# Project_Node_Sensors.net
KiCad netlist of a schematic drawn in Altium Designer
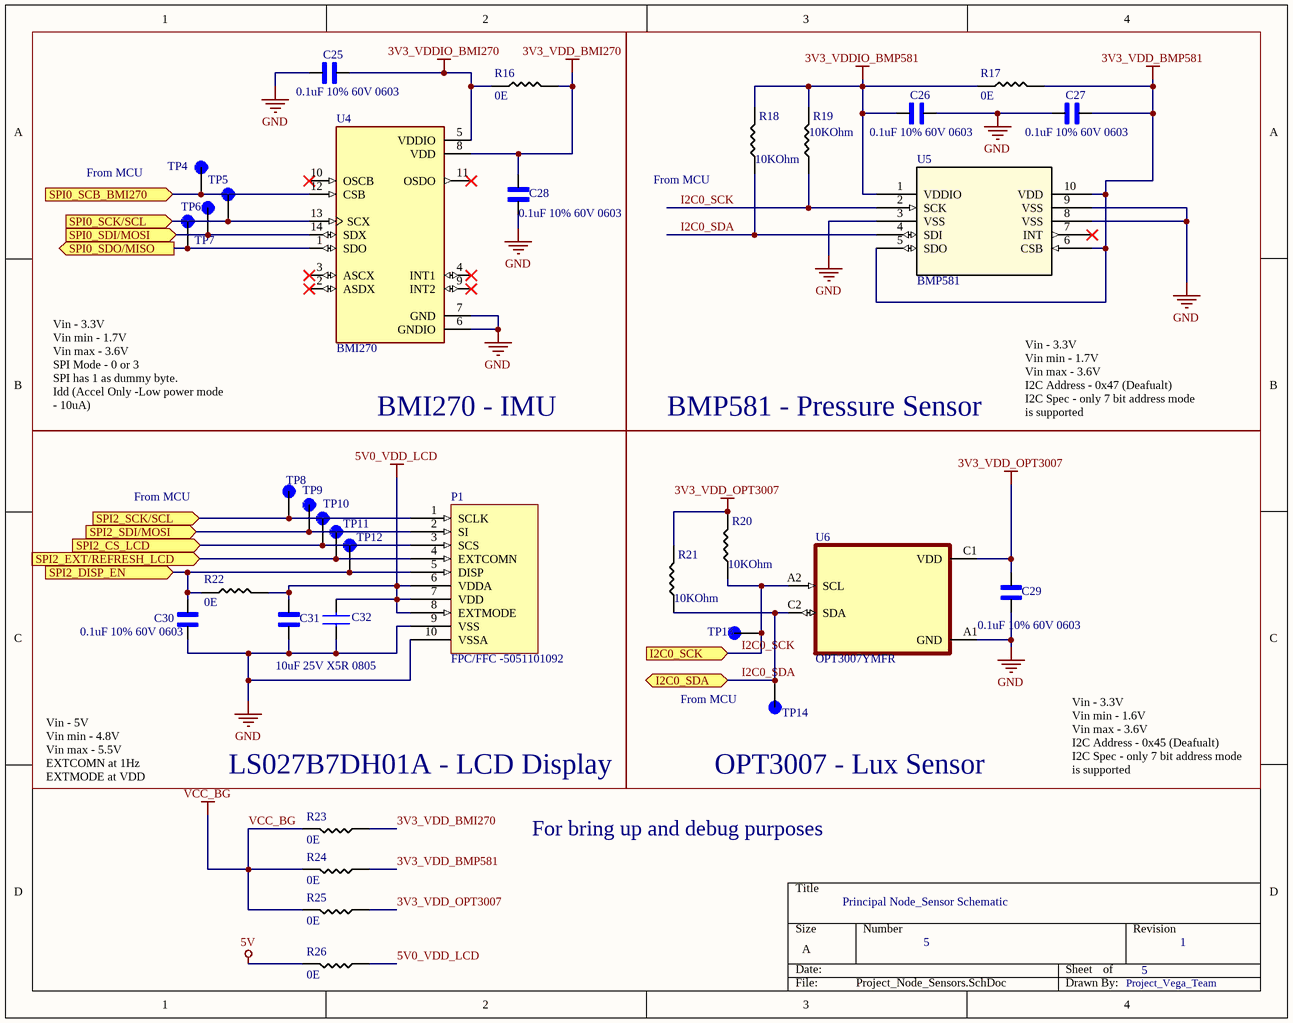
[diagram p0: Project_Node_Sensors.SchDoc]

(export (version "E")
  (design (tool "Eeschema 10.0.6"))
  (components
    (comp (ref "C25")
      (value "0.1uF 10% 60V 0603")
      (footprint "CAPC1608X90")
      (description "0.1 ÂµF Â±10% 50V Ceramic Capacitor X7R 0603 (1608 Metric)")
      (fields (field (name "MF") "Yageo") (field (name "MP") "CC0603KRX7R9BB104"))
      (libsource (lib "") (part "CC0603KRX7R9BB104_1"))
    )
    (comp (ref "C26")
      (value "0.1uF 10% 60V 0603")
      (footprint "CAPC1608X90")
      (description "0.1 ÂµF Â±10% 50V Ceramic Capacitor X7R 0603 (1608 Metric)")
      (fields (field (name "MF") "Yageo") (field (name "MP") "CC0603KRX7R9BB104"))
      (libsource (lib "") (part "CC0603KRX7R9BB104_1"))
    )
    (comp (ref "C27")
      (value "0.1uF 10% 60V 0603")
      (footprint "CAPC1608X90")
      (description "0.1 ÂµF Â±10% 50V Ceramic Capacitor X7R 0603 (1608 Metric)")
      (fields (field (name "MF") "Yageo") (field (name "MP") "CC0603KRX7R9BB104"))
      (libsource (lib "") (part "CC0603KRX7R9BB104_1"))
    )
    (comp (ref "C28")
      (value "0.1uF 10% 60V 0603")
      (footprint "CAPC1608X90")
      (description "0.1 ÂµF Â±10% 50V Ceramic Capacitor X7R 0603 (1608 Metric)")
      (fields (field (name "MF") "Yageo") (field (name "MP") "CC0603KRX7R9BB104"))
      (libsource (lib "") (part "CC0603KRX7R9BB104_2"))
    )
    (comp (ref "C29")
      (value "0.1uF 10% 60V 0603")
      (footprint "CAPC1608X90")
      (description "0.1 ÂµF Â±10% 50V Ceramic Capacitor X7R 0603 (1608 Metric)")
      (fields (field (name "MF") "Yageo") (field (name "MP") "CC0603KRX7R9BB104"))
      (libsource (lib "Project_Vega") (part "CC0603KRX7R9BB104"))
    )
    (comp (ref "C30")
      (value "0.1uF 10% 60V 0603")
      (footprint "CAPC1608X90")
      (description "0.1 ÂµF Â±10% 50V Ceramic Capacitor X7R 0603 (1608 Metric)")
      (fields (field (name "MF") "Yageo") (field (name "MP") "CC0603KRX7R9BB104"))
      (libsource (lib "Project_Vega") (part "CC0603KRX7R9BB104"))
    )
    (comp (ref "C31")
      (value "0.1uF 10% 60V 0603")
      (footprint "CAPC1608X90")
      (description "0.1 ÂµF Â±10% 50V Ceramic Capacitor X7R 0603 (1608 Metric)")
      (fields (field (name "MF") "Yageo") (field (name "MP") "CC0603KRX7R9BB104"))
      (libsource (lib "Project_Vega") (part "CC0603KRX7R9BB104"))
    )
    (comp (ref "C32")
      (value "10uF 25V X5R 0805")
      (footprint "CAP_0805_2mmX1.25mm")
      (description "Multilayer Ceramic Capacitor, 10 uF, 25 V, +/- 10%, X5R, 0805 [2012 Metric]")
      (fields
        (field (name "MANUFACTURER") "Murata")
        (field (name "MANUFACTURER PART NUMBER") "GRM21BR61E106KA73K")
      )
      (libsource (lib "Project_Vega") (part "GRM21BR61E106KA73K"))
    )
    (comp (ref "P1")
      (value "FPC/FFC -5051101092")
      (footprint "CON_5051101092_MOL")
      (description "10 Position FFC, FPC Connector Contacts, Bottom 0.020\" (0.50mm) Surface Mount, Right Angle")
      (libsource (lib "Project_Vega") (part "5051101092"))
    )
    (comp (ref "R16")
      (value "0E")
      (footprint "1206_Passive_Resitor")
      (description "10 kOhms ±5% 0.25W, 1/4W Chip Resistor 1206 (3216 Metric) Automotive AEC-Q200 Thick Film")
      (fields (field (name "MFR PART #") "RMCF1206FT10K0") (field (name "LCSC PART#") "C17902"))
      (libsource (lib "ECEN5730Lib_2023_05_DS") (part "R_10KOhm_1206"))
    )
    (comp (ref "R17")
      (value "0E")
      (footprint "1206_Passive_Resitor")
      (description "10 kOhms ±5% 0.25W, 1/4W Chip Resistor 1206 (3216 Metric) Automotive AEC-Q200 Thick Film")
      (fields (field (name "MFR PART #") "RMCF1206FT10K0") (field (name "LCSC PART#") "C17902"))
      (libsource (lib "ECEN5730Lib_2023_05_DS") (part "R_10KOhm_1206"))
    )
    (comp (ref "R18")
      (value "10KOhm")
      (footprint "1206_Passive_Resitor")
      (description "10 kOhms ±5% 0.25W, 1/4W Chip Resistor 1206 (3216 Metric) Automotive AEC-Q200 Thick Film")
      (fields (field (name "MFR PART #") "RMCF1206FT10K0") (field (name "LCSC PART#") "C17902"))
      (libsource (lib "ECEN5730Lib_2023_05_DS") (part "R_10KOhm_1206"))
    )
    (comp (ref "R19")
      (value "10KOhm")
      (footprint "1206_Passive_Resitor")
      (description "10 kOhms ±5% 0.25W, 1/4W Chip Resistor 1206 (3216 Metric) Automotive AEC-Q200 Thick Film")
      (fields (field (name "MFR PART #") "RMCF1206FT10K0") (field (name "LCSC PART#") "C17902"))
      (libsource (lib "ECEN5730Lib_2023_05_DS") (part "R_10KOhm_1206"))
    )
    (comp (ref "R20")
      (value "10KOhm")
      (footprint "1206_Passive_Resitor")
      (description "10 kOhms ±5% 0.25W, 1/4W Chip Resistor 1206 (3216 Metric) Automotive AEC-Q200 Thick Film")
      (fields (field (name "MFR PART #") "RMCF1206FT10K0") (field (name "LCSC PART#") "C17902"))
      (libsource (lib "ECEN5730Lib_2023_05_DS") (part "R_10KOhm_1206"))
    )
    (comp (ref "R21")
      (value "10KOhm")
      (footprint "1206_Passive_Resitor")
      (description "10 kOhms ±5% 0.25W, 1/4W Chip Resistor 1206 (3216 Metric) Automotive AEC-Q200 Thick Film")
      (fields (field (name "MFR PART #") "RMCF1206FT10K0") (field (name "LCSC PART#") "C17902"))
      (libsource (lib "ECEN5730Lib_2023_05_DS") (part "R_10KOhm_1206"))
    )
    (comp (ref "R22")
      (value "0E")
      (footprint "1206_Passive_Resitor")
      (description "10 kOhms ±5% 0.25W, 1/4W Chip Resistor 1206 (3216 Metric) Automotive AEC-Q200 Thick Film")
      (fields (field (name "MFR PART #") "RMCF1206FT10K0") (field (name "LCSC PART#") "C17902"))
      (libsource (lib "ECEN5730Lib_2023_05_DS") (part "R_10KOhm_1206"))
    )
    (comp (ref "R23")
      (value "0E")
      (footprint "1206_Passive_Resitor")
      (description "10 kOhms ±5% 0.25W, 1/4W Chip Resistor 1206 (3216 Metric) Automotive AEC-Q200 Thick Film")
      (fields (field (name "MFR PART #") "RMCF1206FT10K0") (field (name "LCSC PART#") "C17902"))
      (libsource (lib "ECEN5730Lib_2023_05_DS") (part "R_10KOhm_1206"))
    )
    (comp (ref "R24")
      (value "0E")
      (footprint "1206_Passive_Resitor")
      (description "10 kOhms ±5% 0.25W, 1/4W Chip Resistor 1206 (3216 Metric) Automotive AEC-Q200 Thick Film")
      (fields (field (name "MFR PART #") "RMCF1206FT10K0") (field (name "LCSC PART#") "C17902"))
      (libsource (lib "ECEN5730Lib_2023_05_DS") (part "R_10KOhm_1206"))
    )
    (comp (ref "R25")
      (value "0E")
      (footprint "1206_Passive_Resitor")
      (description "10 kOhms ±5% 0.25W, 1/4W Chip Resistor 1206 (3216 Metric) Automotive AEC-Q200 Thick Film")
      (fields (field (name "MFR PART #") "RMCF1206FT10K0") (field (name "LCSC PART#") "C17902"))
      (libsource (lib "ECEN5730Lib_2023_05_DS") (part "R_10KOhm_1206"))
    )
    (comp (ref "R26")
      (value "0E")
      (footprint "1206_Passive_Resitor")
      (description "10 kOhms ±5% 0.25W, 1/4W Chip Resistor 1206 (3216 Metric) Automotive AEC-Q200 Thick Film")
      (fields (field (name "MFR PART #") "RMCF1206FT10K0") (field (name "LCSC PART#") "C17902"))
      (libsource (lib "ECEN5730Lib_2023_05_DS") (part "R_10KOhm_1206"))
    )
    (comp (ref "TP4")
      (value "Test_point")
      (footprint "TP")
      (description "SMT Test Point- Mininature-1000 pc Reels")
      (fields (field (name "MP") "5019") (field (name "MF") "Keystone Electronics"))
      (libsource (lib "Project_Vega") (part "Test_point"))
    )
    (comp (ref "TP5")
      (value "Test_point")
      (footprint "TP")
      (description "SMT Test Point- Mininature-1000 pc Reels")
      (fields (field (name "MP") "5019") (field (name "MF") "Keystone Electronics"))
      (libsource (lib "Project_Vega") (part "Test_point"))
    )
    (comp (ref "TP6")
      (value "Test_point")
      (footprint "TP")
      (description "SMT Test Point- Mininature-1000 pc Reels")
      (fields (field (name "MP") "5019") (field (name "MF") "Keystone Electronics"))
      (libsource (lib "Project_Vega") (part "Test_point"))
    )
    (comp (ref "TP7")
      (value "Test_point")
      (footprint "TP")
      (description "SMT Test Point- Mininature-1000 pc Reels")
      (fields (field (name "MP") "5019") (field (name "MF") "Keystone Electronics"))
      (libsource (lib "Project_Vega") (part "Test_point"))
    )
    (comp (ref "TP8")
      (value "Test_point")
      (footprint "TP")
      (description "SMT Test Point- Mininature-1000 pc Reels")
      (fields (field (name "MP") "5019") (field (name "MF") "Keystone Electronics"))
      (libsource (lib "Project_Vega") (part "Test_point"))
    )
    (comp (ref "TP9")
      (value "Test_point")
      (footprint "TP")
      (description "SMT Test Point- Mininature-1000 pc Reels")
      (fields (field (name "MP") "5019") (field (name "MF") "Keystone Electronics"))
      (libsource (lib "Project_Vega") (part "Test_point"))
    )
    (comp (ref "TP10")
      (value "Test_point")
      (footprint "TP")
      (description "SMT Test Point- Mininature-1000 pc Reels")
      (fields (field (name "MP") "5019") (field (name "MF") "Keystone Electronics"))
      (libsource (lib "Project_Vega") (part "Test_point"))
    )
    (comp (ref "TP11")
      (value "Test_point")
      (footprint "TP")
      (description "SMT Test Point- Mininature-1000 pc Reels")
      (fields (field (name "MP") "5019") (field (name "MF") "Keystone Electronics"))
      (libsource (lib "Project_Vega") (part "Test_point"))
    )
    (comp (ref "TP12")
      (value "Test_point")
      (footprint "TP")
      (description "SMT Test Point- Mininature-1000 pc Reels")
      (fields (field (name "MP") "5019") (field (name "MF") "Keystone Electronics"))
      (libsource (lib "Project_Vega") (part "Test_point"))
    )
    (comp (ref "TP13")
      (value "Test_point")
      (footprint "TP")
      (description "SMT Test Point- Mininature-1000 pc Reels")
      (fields (field (name "MP") "5019") (field (name "MF") "Keystone Electronics"))
      (libsource (lib "Project_Vega") (part "Test_point"))
    )
    (comp (ref "TP14")
      (value "Test_point")
      (footprint "TP")
      (description "SMT Test Point- Mininature-1000 pc Reels")
      (fields (field (name "MP") "5019") (field (name "MF") "Keystone Electronics"))
      (libsource (lib "Project_Vega") (part "Test_point"))
    )
    (comp (ref "U4")
      (value "BMI270")
      (footprint "XDCR_BMI270")
      (description "Accelerometer, Gyroscope, 6 Axis Sensor IÂ²C, SPI Output")
      (fields (field (name "DIGI-KEY_PART_NUMBER") "828-1091-2-ND") (field (name "MF") "Bosch Sensortec"))
      (libsource (lib "Project_Vega") (part "BMI270"))
    )
    (comp (ref "U5")
      (value "BMP581")
      (footprint "QFN10_BMP581_BOS-M")
      (description "No Description Available")
      (libsource (lib "Project_Vega") (part "BMP581"))
    )
    (comp (ref "U6")
      (value "OPT3007YMFR")
      (footprint "BGA6N60X35P2X3_85X94X22N")
      (description "Ultra-thin ambient light sensor (ALS) with fixed I2C address 6-PICOSTAR -40 to 85")
      (fields (field (name "MF") "Texas Instruments"))
      (libsource (lib "Project_Vega") (part "OPT3007YMFR"))
    )
  )
  (nets
    (net (code "1") (name "/I2C0_SCK") (class "Default")
      (node (ref "R19") (pin "1") (pinfunction "1_1") (pintype "passive"))
      (node (ref "R20") (pin "1") (pinfunction "1_1") (pintype "passive"))
      (node (ref "TP13") (pin "TP") (pinfunction "TP_TP") (pintype "passive"))
      (node (ref "U5") (pin "2") (pinfunction "SCK_2") (pintype "input"))
      (node (ref "U6") (pin "A2") (pinfunction "SCL_A2") (pintype "input"))
    )
    (net (code "2") (name "/I2C0_SDA") (class "Default")
      (node (ref "R18") (pin "1") (pinfunction "1_1") (pintype "passive"))
      (node (ref "R21") (pin "1") (pinfunction "1_1") (pintype "passive"))
      (node (ref "TP14") (pin "TP") (pinfunction "TP_TP") (pintype "passive"))
      (node (ref "U5") (pin "4") (pinfunction "SDI_4") (pintype "bidirectional"))
      (node (ref "U6") (pin "C2") (pinfunction "SDA_C2") (pintype "bidirectional"))
    )
    (net (code "3") (name "/SPI0_SCB_BMI270") (class "Default")
      (node (ref "TP4") (pin "TP") (pinfunction "TP_TP") (pintype "passive"))
      (node (ref "U4") (pin "12") (pinfunction "CSB_12") (pintype "input"))
    )
    (net (code "4") (name "/SPI0_SCK{slash}SCL") (class "Default")
      (node (ref "TP5") (pin "TP") (pinfunction "TP_TP") (pintype "passive"))
      (node (ref "U4") (pin "13") (pinfunction "SCX_13") (pintype "input"))
    )
    (net (code "5") (name "/SPI0_SDI{slash}MOSI") (class "Default")
      (node (ref "TP6") (pin "TP") (pinfunction "TP_TP") (pintype "passive"))
      (node (ref "U4") (pin "14") (pinfunction "SDX_14") (pintype "bidirectional"))
    )
    (net (code "6") (name "/SPI0_SDO{slash}MISO") (class "Default")
      (node (ref "TP7") (pin "TP") (pinfunction "TP_TP") (pintype "passive"))
      (node (ref "U4") (pin "1") (pinfunction "SDO_1") (pintype "bidirectional"))
    )
    (net (code "7") (name "/SPI2_CS_LCD") (class "Default")
      (node (ref "P1") (pin "3") (pinfunction "SCS_3") (pintype "input"))
      (node (ref "TP10") (pin "TP") (pinfunction "TP_TP") (pintype "passive"))
    )
    (net (code "8") (name "/SPI2_DISP_EN") (class "Default")
      (node (ref "C30") (pin "2") (pinfunction "2_2") (pintype "passive"))
      (node (ref "P1") (pin "5") (pinfunction "DISP_5") (pintype "input"))
      (node (ref "R22") (pin "1") (pinfunction "1_1") (pintype "passive"))
      (node (ref "TP12") (pin "TP") (pinfunction "TP_TP") (pintype "passive"))
    )
    (net (code "9") (name "/SPI2_EXT{slash}REFRESH_LCD") (class "Default")
      (node (ref "P1") (pin "4") (pinfunction "EXTCOMN_4") (pintype "input"))
      (node (ref "TP11") (pin "TP") (pinfunction "TP_TP") (pintype "passive"))
    )
    (net (code "10") (name "/SPI2_SCK{slash}SCL") (class "Default")
      (node (ref "P1") (pin "1") (pinfunction "SCLK_1") (pintype "input"))
      (node (ref "TP8") (pin "TP") (pinfunction "TP_TP") (pintype "passive"))
    )
    (net (code "11") (name "/SPI2_SDI{slash}MOSI") (class "Default")
      (node (ref "P1") (pin "2") (pinfunction "SI_2") (pintype "input"))
      (node (ref "TP9") (pin "TP") (pinfunction "TP_TP") (pintype "passive"))
    )
    (net (code "12") (name "3V3_VDDIO_BMI270") (class "Default")
      (node (ref "C25") (pin "2") (pinfunction "2_2") (pintype "passive"))
      (node (ref "R16") (pin "1") (pinfunction "1_1") (pintype "passive"))
      (node (ref "U4") (pin "5") (pinfunction "VDDIO_5") (pintype "power_in"))
    )
    (net (code "13") (name "3V3_VDDIO_BMP581") (class "Default")
      (node (ref "C26") (pin "1") (pinfunction "1_1") (pintype "passive"))
      (node (ref "R17") (pin "1") (pinfunction "1_1") (pintype "passive"))
      (node (ref "R18") (pin "2") (pinfunction "2_2") (pintype "passive"))
      (node (ref "R19") (pin "2") (pinfunction "2_2") (pintype "passive"))
      (node (ref "U5") (pin "1") (pinfunction "VDDIO_1") (pintype "power_in"))
    )
    (net (code "14") (name "3V3_VDD_BMI270") (class "Default")
      (node (ref "C28") (pin "1") (pinfunction "1_1") (pintype "passive"))
      (node (ref "R16") (pin "2") (pinfunction "2_2") (pintype "passive"))
      (node (ref "R23") (pin "1") (pinfunction "1_1") (pintype "passive"))
      (node (ref "U4") (pin "8") (pinfunction "VDD_8") (pintype "power_in"))
    )
    (net (code "15") (name "3V3_VDD_BMP581") (class "Default")
      (node (ref "C27") (pin "2") (pinfunction "2_2") (pintype "passive"))
      (node (ref "R17") (pin "2") (pinfunction "2_2") (pintype "passive"))
      (node (ref "R24") (pin "1") (pinfunction "1_1") (pintype "passive"))
      (node (ref "U5") (pin "10") (pinfunction "VDD_10") (pintype "power_in"))
      (node (ref "U5") (pin "5") (pinfunction "SDO_5") (pintype "bidirectional"))
      (node (ref "U5") (pin "6") (pinfunction "CSB_6") (pintype "input"))
    )
    (net (code "16") (name "3V3_VDD_OPT3007") (class "Default")
      (node (ref "C29") (pin "2") (pinfunction "2_2") (pintype "passive"))
      (node (ref "R20") (pin "2") (pinfunction "2_2") (pintype "passive"))
      (node (ref "R21") (pin "2") (pinfunction "2_2") (pintype "passive"))
      (node (ref "R25") (pin "1") (pinfunction "1_1") (pintype "passive"))
      (node (ref "U6") (pin "C1") (pinfunction "VDD_C1") (pintype "power_in"))
    )
    (net (code "17") (name "5V") (class "Default")
      (node (ref "R26") (pin "2") (pinfunction "2_2") (pintype "passive"))
    )
    (net (code "18") (name "5V0_VDD_LCD") (class "Default")
      (node (ref "C31") (pin "2") (pinfunction "2_2") (pintype "passive"))
      (node (ref "C32") (pin "1") (pinfunction "1_1") (pintype "passive"))
      (node (ref "P1") (pin "6") (pinfunction "VDDA_6") (pintype "power_in"))
      (node (ref "P1") (pin "7") (pinfunction "VDD_7") (pintype "power_in"))
      (node (ref "P1") (pin "8") (pinfunction "EXTMODE_8") (pintype "input"))
      (node (ref "R22") (pin "2") (pinfunction "2_2") (pintype "passive"))
      (node (ref "R26") (pin "1") (pinfunction "1_1") (pintype "passive"))
    )
    (net (code "19") (name "GND") (class "Default")
      (node (ref "C25") (pin "1") (pinfunction "1_1") (pintype "passive"))
      (node (ref "C26") (pin "2") (pinfunction "2_2") (pintype "passive"))
      (node (ref "C27") (pin "1") (pinfunction "1_1") (pintype "passive"))
      (node (ref "C28") (pin "2") (pinfunction "2_2") (pintype "passive"))
      (node (ref "C29") (pin "1") (pinfunction "1_1") (pintype "passive"))
      (node (ref "C30") (pin "1") (pinfunction "1_1") (pintype "passive"))
      (node (ref "C31") (pin "1") (pinfunction "1_1") (pintype "passive"))
      (node (ref "C32") (pin "2") (pinfunction "2_2") (pintype "passive"))
      (node (ref "P1") (pin "10") (pinfunction "VSSA_10") (pintype "power_in"))
      (node (ref "P1") (pin "9") (pinfunction "VSS_9") (pintype "power_in"))
      (node (ref "U4") (pin "6") (pinfunction "GNDIO_6") (pintype "power_in"))
      (node (ref "U4") (pin "7") (pinfunction "GND_7") (pintype "power_in"))
      (node (ref "U5") (pin "3") (pinfunction "VSS_3") (pintype "power_in"))
      (node (ref "U5") (pin "8") (pinfunction "VSS_8") (pintype "power_in"))
      (node (ref "U5") (pin "9") (pinfunction "VSS_9") (pintype "power_in"))
      (node (ref "U6") (pin "A1") (pinfunction "GND_A1") (pintype "power_in"))
    )
    (net (code "20") (name "VCC_BG") (class "Default")
      (node (ref "R23") (pin "2") (pinfunction "2_2") (pintype "passive"))
      (node (ref "R24") (pin "2") (pinfunction "2_2") (pintype "passive"))
      (node (ref "R25") (pin "2") (pinfunction "2_2") (pintype "passive"))
    )
    (net (code "21") (name "unconnected-(U4-ASCX-Pad3)") (class "Default")
      (node (ref "U4") (pin "3") (pinfunction "ASCX_3") (pintype "bidirectional+no_connect"))
    )
    (net (code "22") (name "unconnected-(U4-ASDX-Pad2)") (class "Default")
      (node (ref "U4") (pin "2") (pinfunction "ASDX_2") (pintype "bidirectional+no_connect"))
    )
    (net (code "23") (name "unconnected-(U4-INT1-Pad4)") (class "Default")
      (node (ref "U4") (pin "4") (pinfunction "INT1_4") (pintype "bidirectional+no_connect"))
    )
    (net (code "24") (name "unconnected-(U4-INT2-Pad9)") (class "Default")
      (node (ref "U4") (pin "9") (pinfunction "INT2_9") (pintype "bidirectional+no_connect"))
    )
    (net (code "25") (name "unconnected-(U4-OSCB-Pad10)") (class "Default")
      (node (ref "U4") (pin "10") (pinfunction "OSCB_10") (pintype "input+no_connect"))
    )
    (net (code "26") (name "unconnected-(U4-OSDO-Pad11)") (class "Default")
      (node (ref "U4") (pin "11") (pinfunction "OSDO_11") (pintype "output+no_connect"))
    )
    (net (code "27") (name "unconnected-(U5-INT-Pad7)") (class "Default")
      (node (ref "U5") (pin "7") (pinfunction "INT_7") (pintype "output+no_connect"))
    )
  )
)
